# FTDIProgrammer.net
KiCad netlist of a schematic drawn in Altium Designer
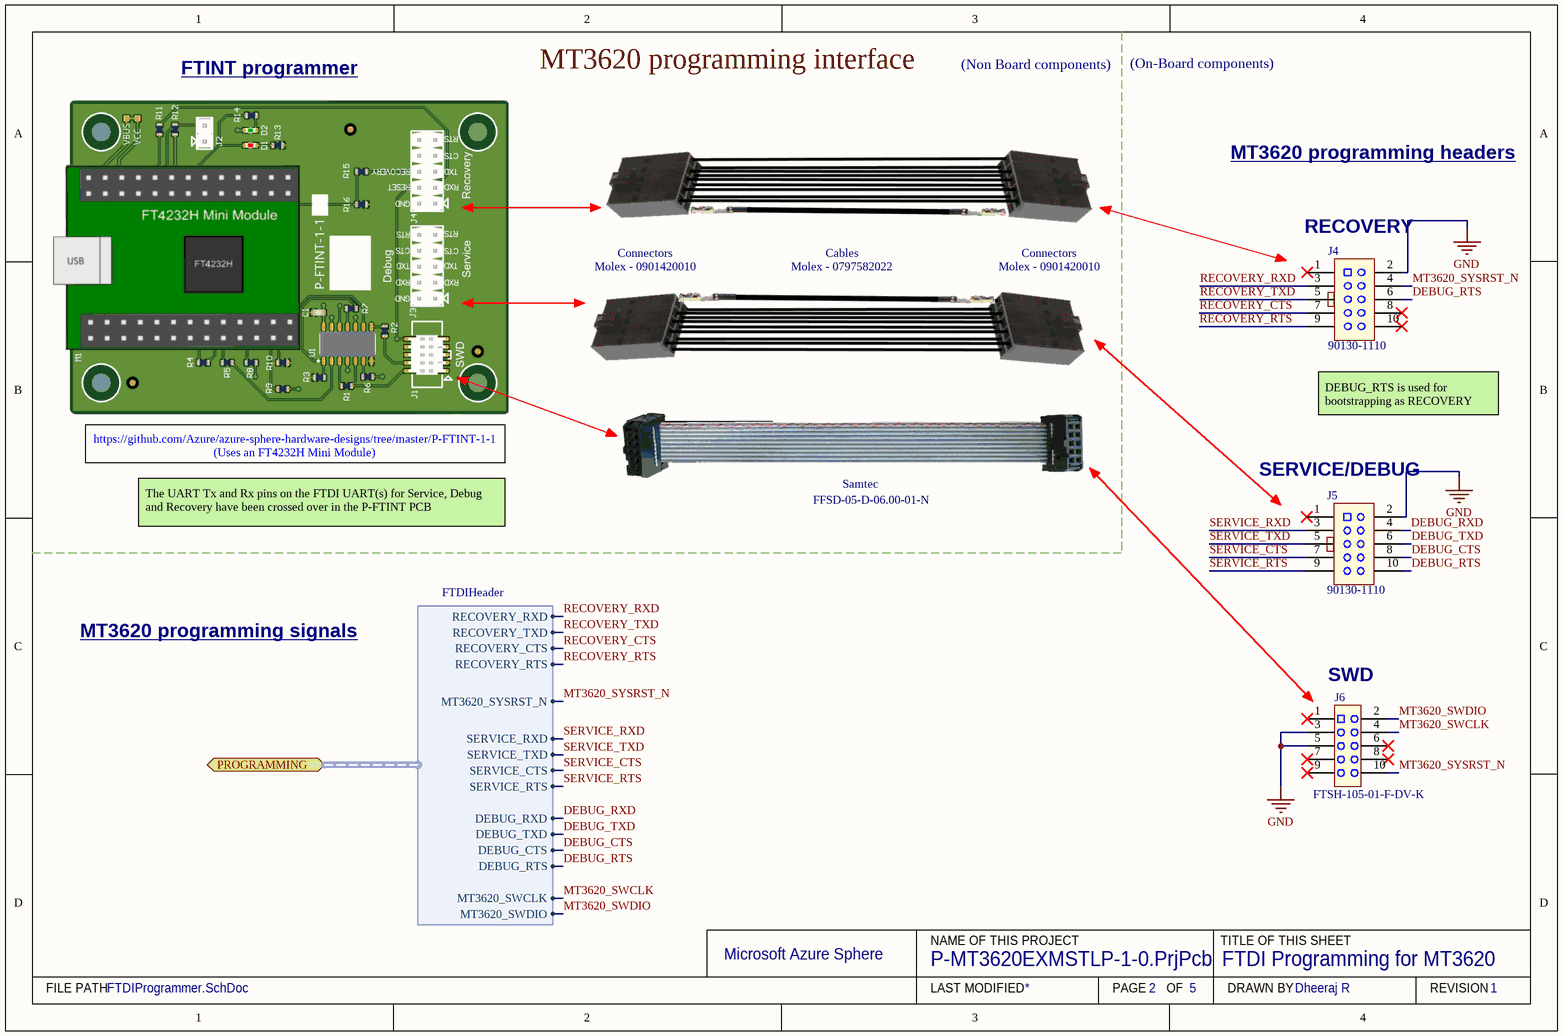
[diagram p0: FTDIProgrammer.SchDoc]

(export (version "E")
  (design (tool "Eeschema 10.0.6"))
  (components
    (comp (ref "J4")
      (value "90130-1110")
      (footprint "0901301110")
      (description "Conn Shrouded Header HDR 10 POS 2.54mm Solder ST Thru-Hole Tray")
      (fields (field (name "MANUFACTURER") "Molex"))
      (libsource (lib "Molex") (part "MOLEX-901301110"))
    )
    (comp (ref "J5")
      (value "90130-1110")
      (footprint "0901301110")
      (description "Conn Shrouded Header HDR 10 POS 2.54mm Solder ST Thru-Hole Tray")
      (fields (field (name "MANUFACTURER") "Molex"))
      (libsource (lib "Molex") (part "MOLEX-901301110"))
    )
    (comp (ref "J6")
      (value "FTSH-105-01-F-DV-K")
      (footprint "SAMTEC-FTSH-105-01-X-DV-K")
      (description "CONN HEADER 10POS DUAL .05\" SMD")
      (fields (field (name "MANUFACTURER") "Samtec Inc."))
      (libsource (lib "Samtec") (part "FTSH-105-01-F-DV-K"))
    )
  )
  (nets
    (net (code "2") (name "/DEBUG_CTS") (class "Default")
      (node (ref "J5") (pin "8") (pinfunction "8_8") (pintype "passive"))
    )
    (net (code "3") (name "/DEBUG_RTS") (class "Default")
      (node (ref "J4") (pin "6") (pinfunction "6_6") (pintype "passive"))
      (node (ref "J5") (pin "10") (pinfunction "10_10") (pintype "passive"))
    )
    (net (code "4") (name "/DEBUG_RXD") (class "Default")
      (node (ref "J5") (pin "4") (pinfunction "4_4") (pintype "passive"))
    )
    (net (code "5") (name "/DEBUG_TXD") (class "Default")
      (node (ref "J5") (pin "6") (pinfunction "6_6") (pintype "passive"))
    )
    (net (code "6") (name "/MT3620_SWCLK") (class "Default")
      (node (ref "J6") (pin "4") (pinfunction "4_4") (pintype "passive"))
    )
    (net (code "7") (name "/MT3620_SWDIO") (class "Default")
      (node (ref "J6") (pin "2") (pinfunction "2_2") (pintype "passive"))
    )
    (net (code "8") (name "/MT3620_SYSRST_N") (class "Default")
      (node (ref "J4") (pin "4") (pinfunction "4_4") (pintype "passive"))
      (node (ref "J6") (pin "10") (pinfunction "10_10") (pintype "passive"))
    )
    (net (code "9") (name "/RECOVERY_CTS") (class "Default")
      (node (ref "J4") (pin "7") (pinfunction "7_7") (pintype "passive"))
    )
    (net (code "10") (name "/RECOVERY_RTS") (class "Default")
      (node (ref "J4") (pin "9") (pinfunction "9_9") (pintype "passive"))
    )
    (net (code "11") (name "/RECOVERY_RXD") (class "Default")
      (node (ref "J4") (pin "3") (pinfunction "3_3") (pintype "passive"))
    )
    (net (code "12") (name "/RECOVERY_TXD") (class "Default")
      (node (ref "J4") (pin "5") (pinfunction "5_5") (pintype "passive"))
    )
    (net (code "13") (name "/SERVICE_CTS") (class "Default")
      (node (ref "J5") (pin "7") (pinfunction "7_7") (pintype "passive"))
    )
    (net (code "14") (name "/SERVICE_RTS") (class "Default")
      (node (ref "J5") (pin "9") (pinfunction "9_9") (pintype "passive"))
    )
    (net (code "15") (name "/SERVICE_RXD") (class "Default")
      (node (ref "J5") (pin "3") (pinfunction "3_3") (pintype "passive"))
    )
    (net (code "16") (name "/SERVICE_TXD") (class "Default")
      (node (ref "J5") (pin "5") (pinfunction "5_5") (pintype "passive"))
    )
    (net (code "18") (name "GND") (class "Default")
      (node (ref "J4") (pin "2") (pinfunction "2_2") (pintype "passive"))
      (node (ref "J5") (pin "2") (pinfunction "2_2") (pintype "passive"))
      (node (ref "J6") (pin "3") (pinfunction "3_3") (pintype "passive"))
      (node (ref "J6") (pin "5") (pinfunction "5_5") (pintype "passive"))
    )
    (net (code "19") (name "unconnected-(J4-Pad1)") (class "Default")
      (node (ref "J4") (pin "1") (pinfunction "1_1") (pintype "passive+no_connect"))
    )
    (net (code "20") (name "unconnected-(J4-Pad8)") (class "Default")
      (node (ref "J4") (pin "8") (pinfunction "8_8") (pintype "passive+no_connect"))
    )
    (net (code "21") (name "unconnected-(J4-Pad10)") (class "Default")
      (node (ref "J4") (pin "10") (pinfunction "10_10") (pintype "passive+no_connect"))
    )
    (net (code "22") (name "unconnected-(J5-Pad1)") (class "Default")
      (node (ref "J5") (pin "1") (pinfunction "1_1") (pintype "passive+no_connect"))
    )
    (net (code "23") (name "unconnected-(J6-Pad1)") (class "Default")
      (node (ref "J6") (pin "1") (pinfunction "1_1") (pintype "passive+no_connect"))
    )
    (net (code "24") (name "unconnected-(J6-Pad6)") (class "Default")
      (node (ref "J6") (pin "6") (pinfunction "6_6") (pintype "passive+no_connect"))
    )
    (net (code "25") (name "unconnected-(J6-Pad7)") (class "Default")
      (node (ref "J6") (pin "7") (pinfunction "7_7") (pintype "passive+no_connect"))
    )
    (net (code "26") (name "unconnected-(J6-Pad8)") (class "Default")
      (node (ref "J6") (pin "8") (pinfunction "8_8") (pintype "passive+no_connect"))
    )
    (net (code "27") (name "unconnected-(J6-Pad9)") (class "Default")
      (node (ref "J6") (pin "9") (pinfunction "9_9") (pintype "passive+no_connect"))
    )
  )
)
